# csc.net
KiCad netlist of a schematic drawn in EAGLE
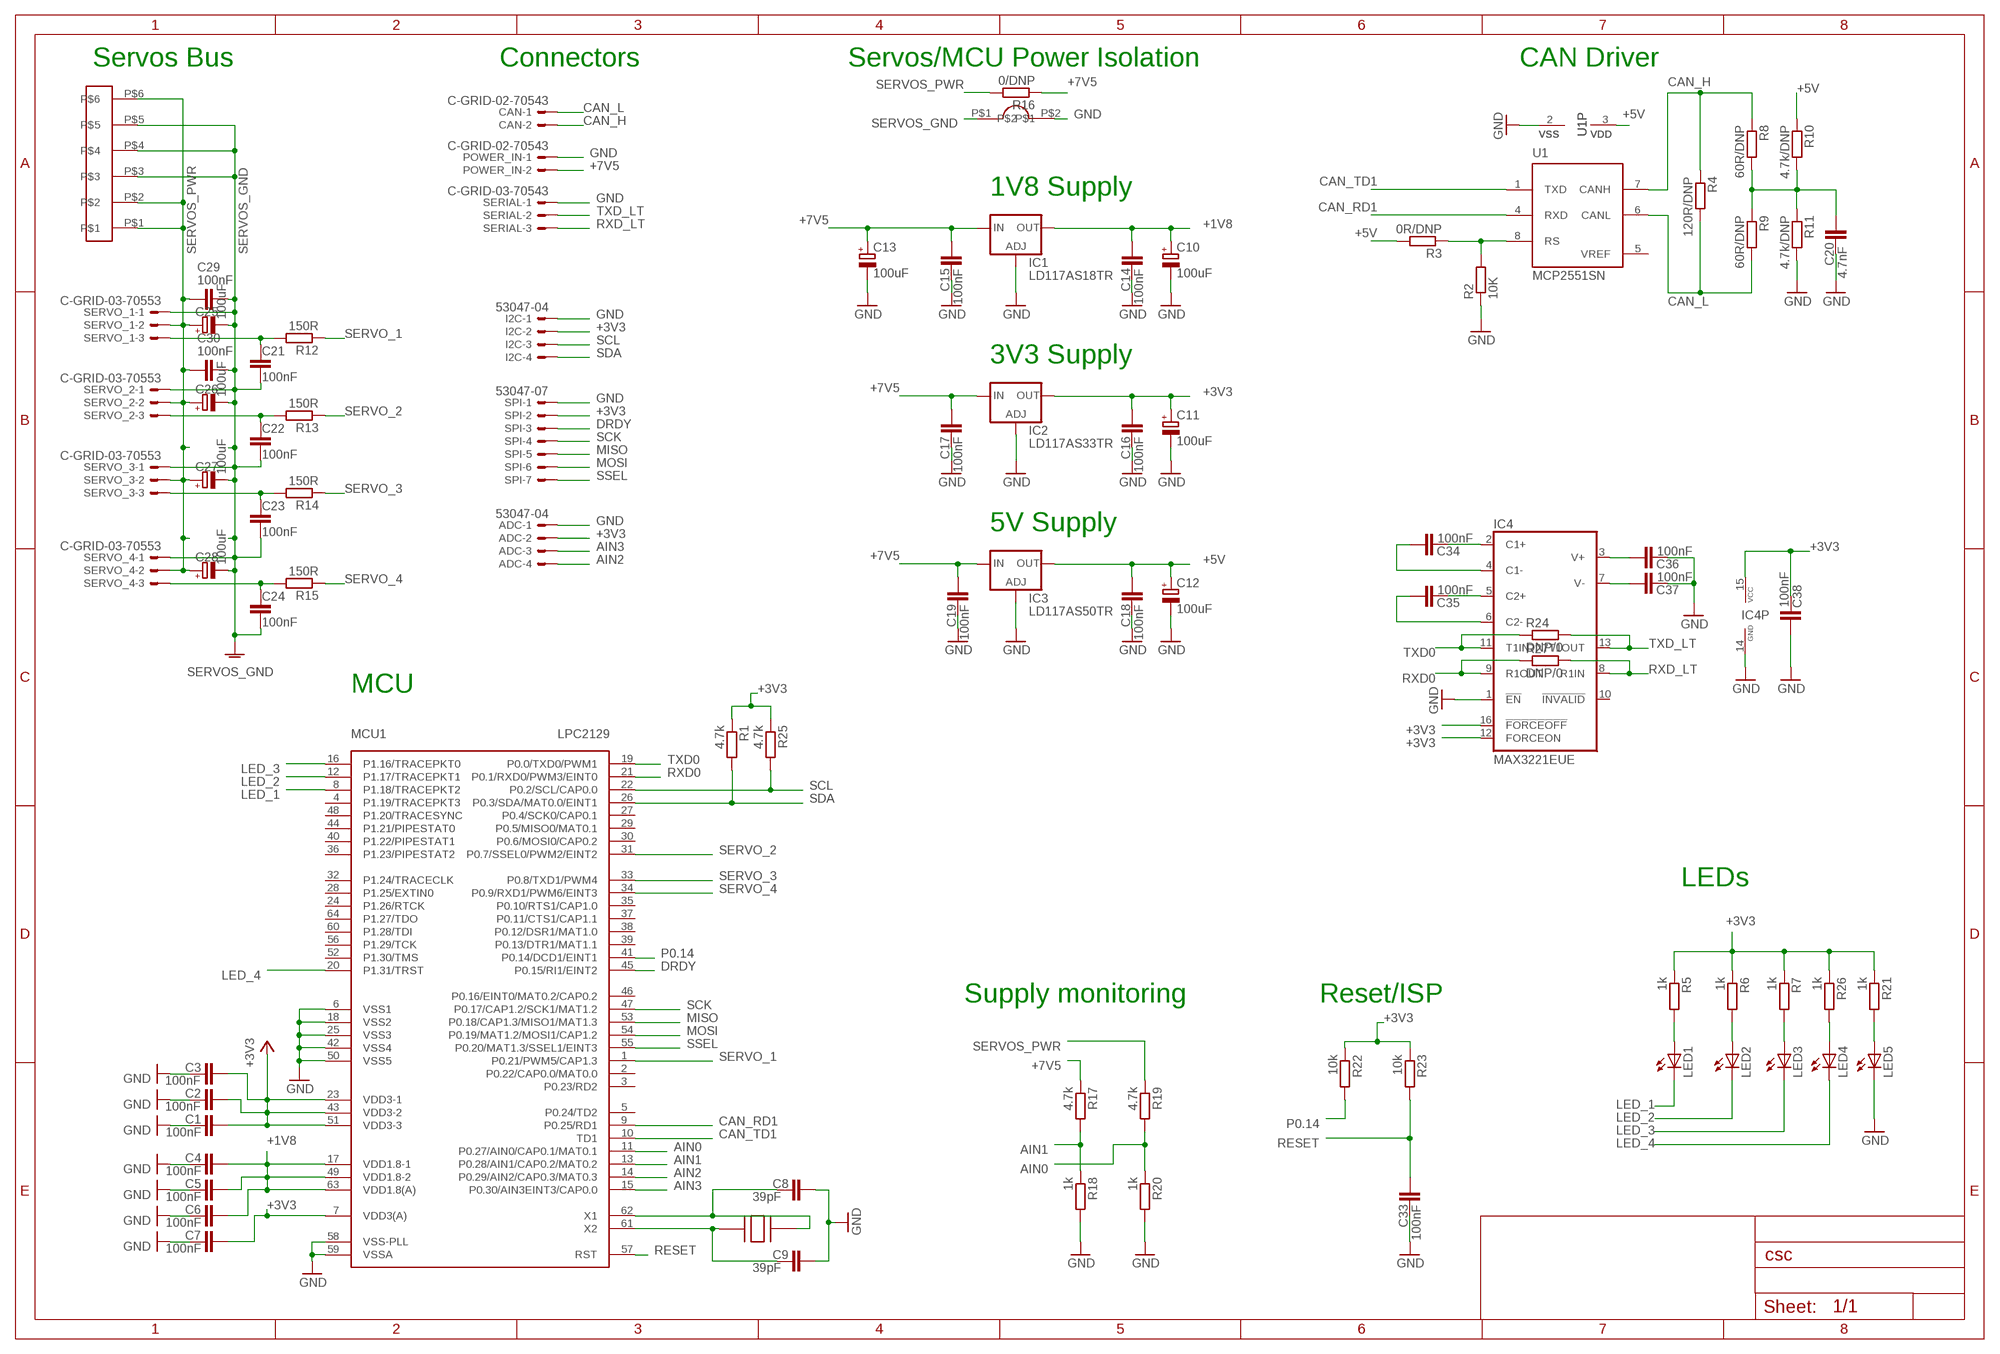
[diagram p0: schematic, sheet 1]

(export (version "E")
  (design (tool "Eeschema 10.0.6"))
  (components
    (comp (ref "ADC")
      (value "53047-04")
      (footprint "eagle-import:53047-04")
      (libsource (lib "eagle-import") (part "53?-04047"))
    )
    (comp (ref "C1")
      (value "100nF")
      (footprint "eagle-import:C0603K")
      (libsource (lib "eagle-import") (part "C-EUC0603K"))
    )
    (comp (ref "C2")
      (value "100nF")
      (footprint "eagle-import:C0603K")
      (libsource (lib "eagle-import") (part "C-EUC0603K"))
    )
    (comp (ref "C3")
      (value "100nF")
      (footprint "eagle-import:C0603K")
      (libsource (lib "eagle-import") (part "C-EUC0603K"))
    )
    (comp (ref "C4")
      (value "100nF")
      (footprint "eagle-import:C0603K")
      (libsource (lib "eagle-import") (part "C-EUC0603K"))
    )
    (comp (ref "C5")
      (value "100nF")
      (footprint "eagle-import:C0603K")
      (libsource (lib "eagle-import") (part "C-EUC0603K"))
    )
    (comp (ref "C6")
      (value "100nF")
      (footprint "eagle-import:C0603K")
      (libsource (lib "eagle-import") (part "C-EUC0603K"))
    )
    (comp (ref "C7")
      (value "100nF")
      (footprint "eagle-import:C0603K")
      (libsource (lib "eagle-import") (part "C-EUC0603K"))
    )
    (comp (ref "C8")
      (value "39pF")
      (footprint "eagle-import:C0603K")
      (libsource (lib "eagle-import") (part "C-EUC0603K"))
    )
    (comp (ref "C9")
      (value "39pF")
      (footprint "eagle-import:C0603K")
      (libsource (lib "eagle-import") (part "C-EUC0603K"))
    )
    (comp (ref "C10")
      (value "100uF")
      (footprint "eagle-import:CT6032")
      (libsource (lib "eagle-import") (part "CPOL-EUCT6032"))
    )
    (comp (ref "C11")
      (value "100uF")
      (footprint "eagle-import:CT6032")
      (libsource (lib "eagle-import") (part "CPOL-EUCT6032"))
    )
    (comp (ref "C12")
      (value "100uF")
      (footprint "eagle-import:CT6032")
      (libsource (lib "eagle-import") (part "CPOL-EUCT6032"))
    )
    (comp (ref "C13")
      (value "100uF")
      (footprint "eagle-import:CT7343")
      (libsource (lib "eagle-import") (part "CPOL-EUCT7343"))
    )
    (comp (ref "C14")
      (value "100nF")
      (footprint "eagle-import:C0603K")
      (libsource (lib "eagle-import") (part "C-EUC0603K"))
    )
    (comp (ref "C15")
      (value "100nF")
      (footprint "eagle-import:C0603K")
      (libsource (lib "eagle-import") (part "C-EUC0603K"))
    )
    (comp (ref "C16")
      (value "100nF")
      (footprint "eagle-import:C0603K")
      (libsource (lib "eagle-import") (part "C-EUC0603K"))
    )
    (comp (ref "C17")
      (value "100nF")
      (footprint "eagle-import:C0603K")
      (libsource (lib "eagle-import") (part "C-EUC0603K"))
    )
    (comp (ref "C18")
      (value "100nF")
      (footprint "eagle-import:C0603K")
      (libsource (lib "eagle-import") (part "C-EUC0603K"))
    )
    (comp (ref "C19")
      (value "100nF")
      (footprint "eagle-import:C0603K")
      (libsource (lib "eagle-import") (part "C-EUC0603K"))
    )
    (comp (ref "C20")
      (value "4.7nF")
      (footprint "eagle-import:C0603K")
      (libsource (lib "eagle-import") (part "C-EUC0603K"))
    )
    (comp (ref "C21")
      (value "100nF")
      (footprint "eagle-import:C0603K")
      (libsource (lib "eagle-import") (part "C-EUC0603K"))
    )
    (comp (ref "C22")
      (value "100nF")
      (footprint "eagle-import:C0603K")
      (libsource (lib "eagle-import") (part "C-EUC0603K"))
    )
    (comp (ref "C23")
      (value "100nF")
      (footprint "eagle-import:C0603K")
      (libsource (lib "eagle-import") (part "C-EUC0603K"))
    )
    (comp (ref "C24")
      (value "100nF")
      (footprint "eagle-import:C0603K")
      (libsource (lib "eagle-import") (part "C-EUC0603K"))
    )
    (comp (ref "C25")
      (value "100uF")
      (footprint "eagle-import:E_7260-38W")
      (libsource (lib "eagle-import") (part "CPOL-EUE/7260-38W"))
    )
    (comp (ref "C26")
      (value "100uF")
      (footprint "eagle-import:E_7260-38W")
      (libsource (lib "eagle-import") (part "CPOL-EUE/7260-38W"))
    )
    (comp (ref "C27")
      (value "100uF")
      (footprint "eagle-import:E_7260-38W")
      (libsource (lib "eagle-import") (part "CPOL-EUE/7260-38W"))
    )
    (comp (ref "C28")
      (value "100uF")
      (footprint "eagle-import:E_7260-38W")
      (libsource (lib "eagle-import") (part "CPOL-EUE/7260-38W"))
    )
    (comp (ref "C29")
      (value "100nF")
      (footprint "eagle-import:C0603K")
      (libsource (lib "eagle-import") (part "C-EUC0603K"))
    )
    (comp (ref "C30")
      (value "100nF")
      (footprint "eagle-import:C0603K")
      (libsource (lib "eagle-import") (part "C-EUC0603K"))
    )
    (comp (ref "C33")
      (value "100nF")
      (footprint "eagle-import:C0603K")
      (libsource (lib "eagle-import") (part "C-EUC0603K"))
    )
    (comp (ref "C34")
      (value "100nF")
      (footprint "eagle-import:C0603K")
      (libsource (lib "eagle-import") (part "C-EUC0603K"))
    )
    (comp (ref "C35")
      (value "100nF")
      (footprint "eagle-import:C0603K")
      (libsource (lib "eagle-import") (part "C-EUC0603K"))
    )
    (comp (ref "C36")
      (value "100nF")
      (footprint "eagle-import:C0603K")
      (libsource (lib "eagle-import") (part "C-EUC0603K"))
    )
    (comp (ref "C37")
      (value "100nF")
      (footprint "eagle-import:C0603K")
      (libsource (lib "eagle-import") (part "C-EUC0603K"))
    )
    (comp (ref "C38")
      (value "100nF")
      (footprint "eagle-import:C0603K")
      (libsource (lib "eagle-import") (part "C-EUC0603K"))
    )
    (comp (ref "CAN")
      (value "C-GRID-02-70543")
      (footprint "eagle-import:70543-02")
      (libsource (lib "eagle-import") (part "C-GRID-02-70543"))
    )
    (comp (ref "I2C")
      (value "53047-04")
      (footprint "eagle-import:53047-04")
      (libsource (lib "eagle-import") (part "53?-04047"))
    )
    (comp (ref "IC1")
      (value "LD117AS18TR")
      (footprint "eagle-import:SOT223")
      (libsource (lib "eagle-import") (part "LD117A?S18TR"))
    )
    (comp (ref "IC2")
      (value "LD117AS33TR")
      (footprint "eagle-import:SOT223")
      (libsource (lib "eagle-import") (part "LD117A?S33TR"))
    )
    (comp (ref "IC3")
      (value "LD117AS50TR")
      (footprint "eagle-import:SOT223")
      (libsource (lib "eagle-import") (part "LD117A?S50TR"))
    )
    (comp (ref "IC4")
      (value "MAX3221EUE")
      (footprint "eagle-import:TSSOP16")
      (libsource (lib "eagle-import") (part "MAX3221UEE"))
    )
    (comp (ref "LED1")
      (value "LEDCHIP-LED0805")
      (footprint "eagle-import:CHIP-LED0805")
      (libsource (lib "eagle-import") (part "LEDCHIP-LED0805"))
    )
    (comp (ref "LED2")
      (value "LEDCHIP-LED0805")
      (footprint "eagle-import:CHIP-LED0805")
      (libsource (lib "eagle-import") (part "LEDCHIP-LED0805"))
    )
    (comp (ref "LED3")
      (value "LEDCHIP-LED0805")
      (footprint "eagle-import:CHIP-LED0805")
      (libsource (lib "eagle-import") (part "LEDCHIP-LED0805"))
    )
    (comp (ref "LED4")
      (value "LEDCHIP-LED0805")
      (footprint "eagle-import:CHIP-LED0805")
      (libsource (lib "eagle-import") (part "LEDCHIP-LED0805"))
    )
    (comp (ref "LED5")
      (value "LEDCHIP-LED0805")
      (footprint "eagle-import:CHIP-LED0805")
      (libsource (lib "eagle-import") (part "LEDCHIP-LED0805"))
    )
    (comp (ref "MCU1")
      (value "LPC2129")
      (footprint "eagle-import:SQFP-S-10X10-64")
      (libsource (lib "eagle-import") (part "LPC2129"))
    )
    (comp (ref "POWER_IN")
      (value "C-GRID-02-70543")
      (footprint "eagle-import:70543-02")
      (libsource (lib "eagle-import") (part "C-GRID-02-70543"))
    )
    (comp (ref "R1")
      (value "4.7k")
      (footprint "eagle-import:R0603")
      (libsource (lib "eagle-import") (part "R-EU_R0603"))
    )
    (comp (ref "R2")
      (value "10K")
      (footprint "eagle-import:R0603")
      (libsource (lib "eagle-import") (part "R-EU_R0603"))
    )
    (comp (ref "R3")
      (value "0R/DNP")
      (footprint "eagle-import:R0603")
      (libsource (lib "eagle-import") (part "R-EU_R0603"))
    )
    (comp (ref "R4")
      (value "120R/DNP")
      (footprint "eagle-import:R0603")
      (libsource (lib "eagle-import") (part "R-EU_R0603"))
    )
    (comp (ref "R5")
      (value "1k")
      (footprint "eagle-import:R0603")
      (libsource (lib "eagle-import") (part "R-EU_R0603"))
    )
    (comp (ref "R6")
      (value "1k")
      (footprint "eagle-import:R0603")
      (libsource (lib "eagle-import") (part "R-EU_R0603"))
    )
    (comp (ref "R7")
      (value "1k")
      (footprint "eagle-import:R0603")
      (libsource (lib "eagle-import") (part "R-EU_R0603"))
    )
    (comp (ref "R8")
      (value "60R/DNP")
      (footprint "eagle-import:R0603")
      (libsource (lib "eagle-import") (part "R-EU_R0603"))
    )
    (comp (ref "R9")
      (value "60R/DNP")
      (footprint "eagle-import:R0603")
      (libsource (lib "eagle-import") (part "R-EU_R0603"))
    )
    (comp (ref "R10")
      (value "4.7k/DNP")
      (footprint "eagle-import:R0603")
      (libsource (lib "eagle-import") (part "R-EU_R0603"))
    )
    (comp (ref "R11")
      (value "4.7k/DNP")
      (footprint "eagle-import:R0603")
      (libsource (lib "eagle-import") (part "R-EU_R0603"))
    )
    (comp (ref "R12")
      (value "150R")
      (footprint "eagle-import:R0603")
      (libsource (lib "eagle-import") (part "R-EU_R0603"))
    )
    (comp (ref "R13")
      (value "150R")
      (footprint "eagle-import:R0603")
      (libsource (lib "eagle-import") (part "R-EU_R0603"))
    )
    (comp (ref "R14")
      (value "150R")
      (footprint "eagle-import:R0603")
      (libsource (lib "eagle-import") (part "R-EU_R0603"))
    )
    (comp (ref "R15")
      (value "150R")
      (footprint "eagle-import:R0603")
      (libsource (lib "eagle-import") (part "R-EU_R0603"))
    )
    (comp (ref "R16")
      (value "0/DNP")
      (footprint "eagle-import:R0603")
      (libsource (lib "eagle-import") (part "R-EU_R0603"))
    )
    (comp (ref "R17")
      (value "4.7k")
      (footprint "eagle-import:R0603")
      (libsource (lib "eagle-import") (part "R-EU_R0603"))
    )
    (comp (ref "R18")
      (value "1k")
      (footprint "eagle-import:R0603")
      (libsource (lib "eagle-import") (part "R-EU_R0603"))
    )
    (comp (ref "R19")
      (value "4.7k")
      (footprint "eagle-import:R0603")
      (libsource (lib "eagle-import") (part "R-EU_R0603"))
    )
    (comp (ref "R20")
      (value "1k")
      (footprint "eagle-import:R0603")
      (libsource (lib "eagle-import") (part "R-EU_R0603"))
    )
    (comp (ref "R21")
      (value "1k")
      (footprint "eagle-import:R0603")
      (libsource (lib "eagle-import") (part "R-EU_R0603"))
    )
    (comp (ref "R22")
      (value "10k")
      (footprint "eagle-import:R0603")
      (libsource (lib "eagle-import") (part "R-EU_R0603"))
    )
    (comp (ref "R23")
      (value "10k")
      (footprint "eagle-import:R0603")
      (libsource (lib "eagle-import") (part "R-EU_R0603"))
    )
    (comp (ref "R24")
      (value "DNP/0")
      (footprint "eagle-import:R0603")
      (libsource (lib "eagle-import") (part "R-EU_R0603"))
    )
    (comp (ref "R25")
      (value "4.7k")
      (footprint "eagle-import:R0603")
      (libsource (lib "eagle-import") (part "R-EU_R0603"))
    )
    (comp (ref "R26")
      (value "1k")
      (footprint "eagle-import:R0603")
      (libsource (lib "eagle-import") (part "R-EU_R0603"))
    )
    (comp (ref "R27")
      (value "DNP/0")
      (footprint "eagle-import:R0603")
      (libsource (lib "eagle-import") (part "R-EU_R0603"))
    )
    (comp (ref "SERIAL")
      (value "C-GRID-03-70543")
      (footprint "eagle-import:70543-03")
      (libsource (lib "eagle-import") (part "C-GRID-03-70543"))
    )
    (comp (ref "SERVO_1")
      (value "C-GRID-03-70553")
      (footprint "eagle-import:70553-03")
      (libsource (lib "eagle-import") (part "C-GRID-03-70553"))
    )
    (comp (ref "SERVO_2")
      (value "C-GRID-03-70553")
      (footprint "eagle-import:70553-03")
      (libsource (lib "eagle-import") (part "C-GRID-03-70553"))
    )
    (comp (ref "SERVO_3")
      (value "C-GRID-03-70553")
      (footprint "eagle-import:70553-03")
      (libsource (lib "eagle-import") (part "C-GRID-03-70553"))
    )
    (comp (ref "SERVO_4")
      (value "C-GRID-03-70553")
      (footprint "eagle-import:70553-03")
      (libsource (lib "eagle-import") (part "C-GRID-03-70553"))
    )
    (comp (ref "SPI")
      (value "53047-07")
      (footprint "eagle-import:53047-07")
      (libsource (lib "eagle-import") (part "53?-07047"))
    )
    (comp (ref "U$1")
      (value "CRYSTAL_CTS")
      (footprint "eagle-import:CTS_CRYSTAL")
      (libsource (lib "eagle-import") (part "CRYSTAL_CTS"))
    )
    (comp (ref "U$2")
      (value "CON_MPX")
      (footprint "eagle-import:CON_MPX")
      (libsource (lib "eagle-import") (part "CON_MPX"))
    )
    (comp (ref "U$3")
      (value "NULL_DEV")
      (footprint "eagle-import:NULL_DEV")
      (libsource (lib "eagle-import") (part "NULL_DEV"))
    )
    (comp (ref "U1")
      (value "MCP2551SN")
      (footprint "eagle-import:SO-08")
      (libsource (lib "eagle-import") (part "MCP2551SN"))
    )
  )
  (nets
    (net (code "1") (name "+3V3") (class "Default")
      (node (ref "ADC") (pin "2") (pinfunction "S_2") (pintype "passive"))
      (node (ref "C1") (pin "2") (pinfunction "2_2") (pintype "passive"))
      (node (ref "C11") (pin "+") (pinfunction "+_+") (pintype "passive"))
      (node (ref "C16") (pin "2") (pinfunction "2_2") (pintype "passive"))
      (node (ref "C2") (pin "2") (pinfunction "2_2") (pintype "passive"))
      (node (ref "C3") (pin "2") (pinfunction "2_2") (pintype "passive"))
      (node (ref "C38") (pin "1") (pinfunction "1_1") (pintype "passive"))
      (node (ref "C7") (pin "2") (pinfunction "2_2") (pintype "passive"))
      (node (ref "I2C") (pin "2") (pinfunction "S_2") (pintype "passive"))
      (node (ref "IC2") (pin "4") (pinfunction "OUT_4") (pintype "passive"))
      (node (ref "IC4") (pin "12") (pinfunction "FORCEON_12") (pintype "input"))
      (node (ref "IC4") (pin "15") (pinfunction "VCC_15") (pintype "power_in"))
      (node (ref "IC4") (pin "16") (pinfunction "~{FORCEOFF}_16") (pintype "input"))
      (node (ref "MCU1") (pin "23") (pinfunction "VDD3-1_23") (pintype "bidirectional"))
      (node (ref "MCU1") (pin "43") (pinfunction "VDD3-2_43") (pintype "bidirectional"))
      (node (ref "MCU1") (pin "51") (pinfunction "VDD3-3_51") (pintype "bidirectional"))
      (node (ref "MCU1") (pin "7") (pinfunction "VDD3(A)_7") (pintype "bidirectional"))
      (node (ref "R1") (pin "1") (pinfunction "1_1") (pintype "passive"))
      (node (ref "R21") (pin "1") (pinfunction "1_1") (pintype "passive"))
      (node (ref "R22") (pin "1") (pinfunction "1_1") (pintype "passive"))
      (node (ref "R23") (pin "1") (pinfunction "1_1") (pintype "passive"))
      (node (ref "R25") (pin "1") (pinfunction "1_1") (pintype "passive"))
      (node (ref "R26") (pin "1") (pinfunction "1_1") (pintype "passive"))
      (node (ref "R5") (pin "1") (pinfunction "1_1") (pintype "passive"))
      (node (ref "R6") (pin "1") (pinfunction "1_1") (pintype "passive"))
      (node (ref "R7") (pin "1") (pinfunction "1_1") (pintype "passive"))
      (node (ref "SPI") (pin "2") (pinfunction "S_2") (pintype "passive"))
    )
    (net (code "2") (name "/+1V8") (class "Default")
      (node (ref "C10") (pin "+") (pinfunction "+_+") (pintype "passive"))
      (node (ref "C14") (pin "2") (pinfunction "2_2") (pintype "passive"))
      (node (ref "C4") (pin "2") (pinfunction "2_2") (pintype "passive"))
      (node (ref "C5") (pin "2") (pinfunction "2_2") (pintype "passive"))
      (node (ref "C6") (pin "2") (pinfunction "2_2") (pintype "passive"))
      (node (ref "IC1") (pin "4") (pinfunction "OUT_4") (pintype "passive"))
      (node (ref "MCU1") (pin "17") (pinfunction "VDD1.8-1_17") (pintype "bidirectional"))
      (node (ref "MCU1") (pin "49") (pinfunction "VDD1.8-2_49") (pintype "bidirectional"))
      (node (ref "MCU1") (pin "63") (pinfunction "VDD1.8(A)_63") (pintype "bidirectional"))
    )
    (net (code "3") (name "/+5V") (class "Default")
      (node (ref "C12") (pin "+") (pinfunction "+_+") (pintype "passive"))
      (node (ref "C18") (pin "2") (pinfunction "2_2") (pintype "passive"))
      (node (ref "IC3") (pin "4") (pinfunction "OUT_4") (pintype "passive"))
      (node (ref "R10") (pin "1") (pinfunction "1_1") (pintype "passive"))
      (node (ref "R3") (pin "2") (pinfunction "2_2") (pintype "passive"))
      (node (ref "U1") (pin "3") (pinfunction "VDD_3") (pintype "power_in"))
    )
    (net (code "4") (name "/+7V5") (class "Default")
      (node (ref "C13") (pin "+") (pinfunction "+_+") (pintype "passive"))
      (node (ref "C15") (pin "2") (pinfunction "2_2") (pintype "passive"))
      (node (ref "C17") (pin "2") (pinfunction "2_2") (pintype "passive"))
      (node (ref "C19") (pin "2") (pinfunction "2_2") (pintype "passive"))
      (node (ref "IC1") (pin "3") (pinfunction "IN_3") (pintype "input"))
      (node (ref "IC2") (pin "3") (pinfunction "IN_3") (pintype "input"))
      (node (ref "IC3") (pin "3") (pinfunction "IN_3") (pintype "input"))
      (node (ref "POWER_IN") (pin "2") (pinfunction "S_2") (pintype "passive"))
      (node (ref "R16") (pin "1") (pinfunction "1_1") (pintype "passive"))
      (node (ref "R17") (pin "1") (pinfunction "1_1") (pintype "passive"))
    )
    (net (code "5") (name "/AIN0") (class "Default")
      (node (ref "MCU1") (pin "11") (pinfunction "P0.27/AIN0/CAP0.1/MAT0.1_11") (pintype "bidirectional"))
      (node (ref "R19") (pin "2") (pinfunction "2_2") (pintype "passive"))
      (node (ref "R20") (pin "1") (pinfunction "1_1") (pintype "passive"))
    )
    (net (code "6") (name "/AIN1") (class "Default")
      (node (ref "MCU1") (pin "13") (pinfunction "P0.28/AIN1/CAP0.2/MAT0.2_13") (pintype "bidirectional"))
      (node (ref "R17") (pin "2") (pinfunction "2_2") (pintype "passive"))
      (node (ref "R18") (pin "1") (pinfunction "1_1") (pintype "passive"))
    )
    (net (code "7") (name "/AIN2") (class "Default")
      (node (ref "ADC") (pin "4") (pinfunction "S_4") (pintype "passive"))
      (node (ref "MCU1") (pin "14") (pinfunction "P0.29/AIN2/CAP0.3/MAT0.3_14") (pintype "bidirectional"))
    )
    (net (code "8") (name "/AIN3") (class "Default")
      (node (ref "ADC") (pin "3") (pinfunction "S_3") (pintype "passive"))
      (node (ref "MCU1") (pin "15") (pinfunction "P0.30/AIN3EINT3/CAP0.0_15") (pintype "bidirectional"))
    )
    (net (code "9") (name "/CAN_H") (class "Default")
      (node (ref "CAN") (pin "2") (pinfunction "S_2") (pintype "passive"))
      (node (ref "R4") (pin "1") (pinfunction "1_1") (pintype "passive"))
      (node (ref "R8") (pin "1") (pinfunction "1_1") (pintype "passive"))
      (node (ref "U1") (pin "7") (pinfunction "CANH_7") (pintype "bidirectional"))
    )
    (net (code "10") (name "/CAN_L") (class "Default")
      (node (ref "CAN") (pin "1") (pinfunction "S_1") (pintype "passive"))
      (node (ref "R4") (pin "2") (pinfunction "2_2") (pintype "passive"))
      (node (ref "R9") (pin "2") (pinfunction "2_2") (pintype "passive"))
      (node (ref "U1") (pin "6") (pinfunction "CANL_6") (pintype "bidirectional"))
    )
    (net (code "11") (name "/CAN_RD1") (class "Default")
      (node (ref "MCU1") (pin "9") (pinfunction "P0.25/RD1_9") (pintype "bidirectional"))
      (node (ref "U1") (pin "4") (pinfunction "RXD_4") (pintype "output"))
    )
    (net (code "12") (name "/CAN_TD1") (class "Default")
      (node (ref "MCU1") (pin "10") (pinfunction "TD1_10") (pintype "bidirectional"))
      (node (ref "U1") (pin "1") (pinfunction "TXD_1") (pintype "input"))
    )
    (net (code "13") (name "/DRDY") (class "Default")
      (node (ref "MCU1") (pin "45") (pinfunction "P0.15/RI1/EINT2_45") (pintype "bidirectional"))
      (node (ref "SPI") (pin "3") (pinfunction "S_3") (pintype "passive"))
    )
    (net (code "14") (name "/LED_1") (class "Default")
      (node (ref "LED1") (pin "C") (pinfunction "C_C") (pintype "passive"))
      (node (ref "MCU1") (pin "8") (pinfunction "P1.18/TRACEPKT2_8") (pintype "bidirectional"))
    )
    (net (code "15") (name "/LED_2") (class "Default")
      (node (ref "LED2") (pin "C") (pinfunction "C_C") (pintype "passive"))
      (node (ref "MCU1") (pin "12") (pinfunction "P1.17/TRACEPKT1_12") (pintype "bidirectional"))
    )
    (net (code "16") (name "/LED_3") (class "Default")
      (node (ref "LED3") (pin "C") (pinfunction "C_C") (pintype "passive"))
      (node (ref "MCU1") (pin "16") (pinfunction "P1.16/TRACEPKT0_16") (pintype "bidirectional"))
    )
    (net (code "17") (name "/LED_4") (class "Default")
      (node (ref "LED4") (pin "C") (pinfunction "C_C") (pintype "passive"))
      (node (ref "MCU1") (pin "20") (pinfunction "P1.31/TRST_20") (pintype "bidirectional"))
    )
    (net (code "18") (name "/MISO") (class "Default")
      (node (ref "MCU1") (pin "53") (pinfunction "P0.18/CAP1.3/MISO1/MAT1.3_53") (pintype "bidirectional"))
      (node (ref "SPI") (pin "5") (pinfunction "S_5") (pintype "passive"))
    )
    (net (code "19") (name "/MOSI") (class "Default")
      (node (ref "MCU1") (pin "54") (pinfunction "P0.19/MAT1.2/MOSI1/CAP1.2_54") (pintype "bidirectional"))
      (node (ref "SPI") (pin "6") (pinfunction "S_6") (pintype "passive"))
    )
    (net (code "20") (name "/P0.14") (class "Default")
      (node (ref "MCU1") (pin "41") (pinfunction "P0.14/DCD1/EINT1_41") (pintype "bidirectional"))
      (node (ref "R22") (pin "2") (pinfunction "2_2") (pintype "passive"))
    )
    (net (code "21") (name "/RESET") (class "Default")
      (node (ref "C33") (pin "2") (pinfunction "2_2") (pintype "passive"))
      (node (ref "MCU1") (pin "57") (pinfunction "RST_57") (pintype "bidirectional"))
      (node (ref "R23") (pin "2") (pinfunction "2_2") (pintype "passive"))
    )
    (net (code "22") (name "/RXD0") (class "Default")
      (node (ref "IC4") (pin "9") (pinfunction "R1OUT_9") (pintype "output"))
      (node (ref "MCU1") (pin "21") (pinfunction "P0.1/RXD0/PWM3/EINT0_21") (pintype "bidirectional"))
      (node (ref "R27") (pin "1") (pinfunction "1_1") (pintype "passive"))
    )
    (net (code "23") (name "/RXD_LT") (class "Default")
      (node (ref "IC4") (pin "8") (pinfunction "R1IN_8") (pintype "input"))
      (node (ref "R27") (pin "2") (pinfunction "2_2") (pintype "passive"))
      (node (ref "SERIAL") (pin "3") (pinfunction "S_3") (pintype "passive"))
    )
    (net (code "24") (name "/SCK") (class "Default")
      (node (ref "MCU1") (pin "47") (pinfunction "P0.17/CAP1.2/SCK1/MAT1.2_47") (pintype "bidirectional"))
      (node (ref "SPI") (pin "4") (pinfunction "S_4") (pintype "passive"))
    )
    (net (code "25") (name "/SCL") (class "Default")
      (node (ref "I2C") (pin "3") (pinfunction "S_3") (pintype "passive"))
      (node (ref "MCU1") (pin "22") (pinfunction "P0.2/SCL/CAP0.0_22") (pintype "bidirectional"))
      (node (ref "R25") (pin "2") (pinfunction "2_2") (pintype "passive"))
    )
    (net (code "26") (name "/SDA") (class "Default")
      (node (ref "I2C") (pin "4") (pinfunction "S_4") (pintype "passive"))
      (node (ref "MCU1") (pin "26") (pinfunction "P0.3/SDA/MAT0.0/EINT1_26") (pintype "bidirectional"))
      (node (ref "R1") (pin "2") (pinfunction "2_2") (pintype "passive"))
    )
    (net (code "27") (name "/SERVOS_PWR") (class "Default")
      (node (ref "C25") (pin "+") (pinfunction "+_+") (pintype "passive"))
      (node (ref "C26") (pin "+") (pinfunction "+_+") (pintype "passive"))
      (node (ref "C27") (pin "+") (pinfunction "+_+") (pintype "passive"))
      (node (ref "C28") (pin "+") (pinfunction "+_+") (pintype "passive"))
      (node (ref "C29") (pin "2") (pinfunction "2_2") (pintype "passive"))
      (node (ref "C30") (pin "2") (pinfunction "2_2") (pintype "passive"))
      (node (ref "R16") (pin "2") (pinfunction "2_2") (pintype "passive"))
      (node (ref "R19") (pin "1") (pinfunction "1_1") (pintype "passive"))
      (node (ref "SERVO_1") (pin "2") (pinfunction "S_2") (pintype "passive"))
      (node (ref "SERVO_2") (pin "2") (pinfunction "S_2") (pintype "passive"))
      (node (ref "SERVO_3") (pin "2") (pinfunction "S_2") (pintype "passive"))
      (node (ref "SERVO_4") (pin "2") (pinfunction "S_2") (pintype "passive"))
      (node (ref "U$2") (pin "P$1") (pinfunction "P$1_P$1") (pintype "bidirectional"))
      (node (ref "U$2") (pin "P$2") (pinfunction "P$2_P$2") (pintype "bidirectional"))
      (node (ref "U$2") (pin "P$6") (pinfunction "P$6_P$6") (pintype "bidirectional"))
    )
    (net (code "28") (name "/SERVO_1") (class "Default")
      (node (ref "MCU1") (pin "1") (pinfunction "P0.21/PWM5/CAP1.3_1") (pintype "bidirectional"))
      (node (ref "R12") (pin "1") (pinfunction "1_1") (pintype "passive"))
    )
    (net (code "29") (name "/SERVO_2") (class "Default")
      (node (ref "MCU1") (pin "31") (pinfunction "P0.7/SSEL0/PWM2/EINT2_31") (pintype "bidirectional"))
      (node (ref "R13") (pin "1") (pinfunction "1_1") (pintype "passive"))
    )
    (net (code "30") (name "/SERVO_3") (class "Default")
      (node (ref "MCU1") (pin "33") (pinfunction "P0.8/TXD1/PWM4_33") (pintype "bidirectional"))
      (node (ref "R14") (pin "1") (pinfunction "1_1") (pintype "passive"))
    )
    (net (code "31") (name "/SERVO_4") (class "Default")
      (node (ref "MCU1") (pin "34") (pinfunction "P0.9/RXD1/PWM6/EINT3_34") (pintype "bidirectional"))
      (node (ref "R15") (pin "1") (pinfunction "1_1") (pintype "passive"))
    )
    (net (code "32") (name "/SSEL") (class "Default")
      (node (ref "MCU1") (pin "55") (pinfunction "P0.20/MAT1.3/SSEL1/EINT3_55") (pintype "bidirectional"))
      (node (ref "SPI") (pin "7") (pinfunction "S_7") (pintype "passive"))
    )
    (net (code "33") (name "/TXD0") (class "Default")
      (node (ref "IC4") (pin "11") (pinfunction "T1IN_11") (pintype "input"))
      (node (ref "MCU1") (pin "19") (pinfunction "P0.0/TXD0/PWM1_19") (pintype "bidirectional"))
      (node (ref "R24") (pin "1") (pinfunction "1_1") (pintype "passive"))
    )
    (net (code "34") (name "/TXD_LT") (class "Default")
      (node (ref "IC4") (pin "13") (pinfunction "T1OUT_13") (pintype "output"))
      (node (ref "R24") (pin "2") (pinfunction "2_2") (pintype "passive"))
      (node (ref "SERIAL") (pin "2") (pinfunction "S_2") (pintype "passive"))
    )
    (net (code "35") (name "/VREF") (class "Default")
      (node (ref "U1") (pin "5") (pinfunction "VREF_5") (pintype "power_in"))
    )
    (net (code "36") (name "GND") (class "Default")
      (node (ref "ADC") (pin "1") (pinfunction "S_1") (pintype "passive"))
      (node (ref "C1") (pin "1") (pinfunction "1_1") (pintype "passive"))
      (node (ref "C10") (pin "-") (pinfunction "-_-") (pintype "passive"))
      (node (ref "C11") (pin "-") (pinfunction "-_-") (pintype "passive"))
      (node (ref "C12") (pin "-") (pinfunction "-_-") (pintype "passive"))
      (node (ref "C13") (pin "-") (pinfunction "-_-") (pintype "passive"))
      (node (ref "C14") (pin "1") (pinfunction "1_1") (pintype "passive"))
      (node (ref "C15") (pin "1") (pinfunction "1_1") (pintype "passive"))
      (node (ref "C16") (pin "1") (pinfunction "1_1") (pintype "passive"))
      (node (ref "C17") (pin "1") (pinfunction "1_1") (pintype "passive"))
      (node (ref "C18") (pin "1") (pinfunction "1_1") (pintype "passive"))
      (node (ref "C19") (pin "1") (pinfunction "1_1") (pintype "passive"))
      (node (ref "C2") (pin "1") (pinfunction "1_1") (pintype "passive"))
      (node (ref "C20") (pin "1") (pinfunction "1_1") (pintype "passive"))
      (node (ref "C3") (pin "1") (pinfunction "1_1") (pintype "passive"))
      (node (ref "C33") (pin "1") (pinfunction "1_1") (pintype "passive"))
      (node (ref "C36") (pin "1") (pinfunction "1_1") (pintype "passive"))
      (node (ref "C37") (pin "1") (pinfunction "1_1") (pintype "passive"))
      (node (ref "C38") (pin "2") (pinfunction "2_2") (pintype "passive"))
      (node (ref "C4") (pin "1") (pinfunction "1_1") (pintype "passive"))
      (node (ref "C5") (pin "1") (pinfunction "1_1") (pintype "passive"))
      (node (ref "C6") (pin "1") (pinfunction "1_1") (pintype "passive"))
      (node (ref "C7") (pin "1") (pinfunction "1_1") (pintype "passive"))
      (node (ref "C8") (pin "2") (pinfunction "2_2") (pintype "passive"))
      (node (ref "C9") (pin "2") (pinfunction "2_2") (pintype "passive"))
      (node (ref "I2C") (pin "1") (pinfunction "S_1") (pintype "passive"))
      (node (ref "IC1") (pin "1") (pinfunction "ADJ_1") (pintype "input"))
      (node (ref "IC2") (pin "1") (pinfunction "ADJ_1") (pintype "input"))
      (node (ref "IC3") (pin "1") (pinfunction "ADJ_1") (pintype "input"))
      (node (ref "IC4") (pin "1") (pinfunction "~{EN}_1") (pintype "input"))
      (node (ref "IC4") (pin "14") (pinfunction "GND_14") (pintype "power_in"))
      (node (ref "LED5") (pin "C") (pinfunction "C_C") (pintype "passive"))
      (node (ref "MCU1") (pin "18") (pinfunction "VSS2_18") (pintype "bidirectional"))
      (node (ref "MCU1") (pin "25") (pinfunction "VSS3_25") (pintype "bidirectional"))
      (node (ref "MCU1") (pin "42") (pinfunction "VSS4_42") (pintype "bidirectional"))
      (node (ref "MCU1") (pin "50") (pinfunction "VSS5_50") (pintype "bidirectional"))
      (node (ref "MCU1") (pin "58") (pinfunction "VSS-PLL_58") (pintype "bidirectional"))
      (node (ref "MCU1") (pin "59") (pinfunction "VSSA_59") (pintype "bidirectional"))
      (node (ref "MCU1") (pin "6") (pinfunction "VSS1_6") (pintype "bidirectional"))
      (node (ref "POWER_IN") (pin "1") (pinfunction "S_1") (pintype "passive"))
      (node (ref "R11") (pin "2") (pinfunction "2_2") (pintype "passive"))
      (node (ref "R18") (pin "2") (pinfunction "2_2") (pintype "passive"))
      (node (ref "R2") (pin "1") (pinfunction "1_1") (pintype "passive"))
      (node (ref "R20") (pin "2") (pinfunction "2_2") (pintype "passive"))
      (node (ref "SERIAL") (pin "1") (pinfunction "S_1") (pintype "passive"))
      (node (ref "SPI") (pin "1") (pinfunction "S_1") (pintype "passive"))
      (node (ref "U$3") (pin "P$2") (pinfunction "P$2_P$2") (pintype "bidirectional"))
      (node (ref "U1") (pin "2") (pinfunction "VSS_2") (pintype "power_in"))
    )
    (net (code "37") (name "Net-(C20-Pad2)") (class "Default")
      (node (ref "C20") (pin "2") (pinfunction "2_2") (pintype "passive"))
      (node (ref "R10") (pin "2") (pinfunction "2_2") (pintype "passive"))
      (node (ref "R11") (pin "1") (pinfunction "1_1") (pintype "passive"))
      (node (ref "R8") (pin "2") (pinfunction "2_2") (pintype "passive"))
      (node (ref "R9") (pin "1") (pinfunction "1_1") (pintype "passive"))
    )
    (net (code "38") (name "Net-(IC4A-C1+)") (class "Default")
      (node (ref "C34") (pin "1") (pinfunction "1_1") (pintype "passive"))
      (node (ref "IC4") (pin "2") (pinfunction "C1+_2") (pintype "passive"))
    )
    (net (code "39") (name "Net-(IC4A-C1-)") (class "Default")
      (node (ref "C34") (pin "2") (pinfunction "2_2") (pintype "passive"))
      (node (ref "IC4") (pin "4") (pinfunction "C1-_4") (pintype "passive"))
    )
    (net (code "40") (name "Net-(IC4A-C2+)") (class "Default")
      (node (ref "C35") (pin "1") (pinfunction "1_1") (pintype "passive"))
      (node (ref "IC4") (pin "5") (pinfunction "C2+_5") (pintype "passive"))
    )
    (net (code "41") (name "Net-(IC4A-C2-)") (class "Default")
      (node (ref "C35") (pin "2") (pinfunction "2_2") (pintype "passive"))
      (node (ref "IC4") (pin "6") (pinfunction "C2-_6") (pintype "passive"))
    )
    (net (code "42") (name "Net-(IC4A-V+)") (class "Default")
      (node (ref "C36") (pin "2") (pinfunction "2_2") (pintype "passive"))
      (node (ref "IC4") (pin "3") (pinfunction "V+_3") (pintype "passive"))
    )
    (net (code "43") (name "Net-(IC4A-V-)") (class "Default")
      (node (ref "C37") (pin "2") (pinfunction "2_2") (pintype "passive"))
      (node (ref "IC4") (pin "7") (pinfunction "V-_7") (pintype "passive"))
    )
    (net (code "44") (name "Net-(LED1-PadA)") (class "Default")
      (node (ref "LED1") (pin "A") (pinfunction "A_A") (pintype "passive"))
      (node (ref "R5") (pin "2") (pinfunction "2_2") (pintype "passive"))
    )
    (net (code "45") (name "Net-(LED2-PadA)") (class "Default")
      (node (ref "LED2") (pin "A") (pinfunction "A_A") (pintype "passive"))
      (node (ref "R6") (pin "2") (pinfunction "2_2") (pintype "passive"))
    )
    (net (code "46") (name "Net-(LED3-PadA)") (class "Default")
      (node (ref "LED3") (pin "A") (pinfunction "A_A") (pintype "passive"))
      (node (ref "R7") (pin "2") (pinfunction "2_2") (pintype "passive"))
    )
    (net (code "47") (name "Net-(LED4-PadA)") (class "Default")
      (node (ref "LED4") (pin "A") (pinfunction "A_A") (pintype "passive"))
      (node (ref "R26") (pin "2") (pinfunction "2_2") (pintype "passive"))
    )
    (net (code "48") (name "Net-(LED5-PadA)") (class "Default")
      (node (ref "LED5") (pin "A") (pinfunction "A_A") (pintype "passive"))
      (node (ref "R21") (pin "2") (pinfunction "2_2") (pintype "passive"))
    )
    (net (code "49") (name "Net-(MCU1-X1)") (class "Default")
      (node (ref "C8") (pin "1") (pinfunction "1_1") (pintype "passive"))
      (node (ref "MCU1") (pin "62") (pinfunction "X1_62") (pintype "bidirectional"))
      (node (ref "U$1") (pin "P$1") (pinfunction "P$1_P$1") (pintype "bidirectional"))
    )
    (net (code "50") (name "Net-(MCU1-X2)") (class "Default")
      (node (ref "C9") (pin "1") (pinfunction "1_1") (pintype "passive"))
      (node (ref "MCU1") (pin "61") (pinfunction "X2_61") (pintype "bidirectional"))
      (node (ref "U$1") (pin "P$3") (pinfunction "P$2_P$3") (pintype "bidirectional"))
    )
    (net (code "51") (name "Net-(SERVO_1C-S)") (class "Default")
      (node (ref "C21") (pin "2") (pinfunction "2_2") (pintype "passive"))
      (node (ref "R12") (pin "2") (pinfunction "2_2") (pintype "passive"))
      (node (ref "SERVO_1") (pin "3") (pinfunction "S_3") (pintype "passive"))
    )
    (net (code "52") (name "Net-(SERVO_2C-S)") (class "Default")
      (node (ref "C22") (pin "2") (pinfunction "2_2") (pintype "passive"))
      (node (ref "R13") (pin "2") (pinfunction "2_2") (pintype "passive"))
      (node (ref "SERVO_2") (pin "3") (pinfunction "S_3") (pintype "passive"))
    )
    (net (code "53") (name "Net-(SERVO_3C-S)") (class "Default")
      (node (ref "C23") (pin "2") (pinfunction "2_2") (pintype "passive"))
      (node (ref "R14") (pin "2") (pinfunction "2_2") (pintype "passive"))
      (node (ref "SERVO_3") (pin "3") (pinfunction "S_3") (pintype "passive"))
    )
    (net (code "54") (name "Net-(SERVO_4C-S)") (class "Default")
      (node (ref "C24") (pin "2") (pinfunction "2_2") (pintype "passive"))
      (node (ref "R15") (pin "2") (pinfunction "2_2") (pintype "passive"))
      (node (ref "SERVO_4") (pin "3") (pinfunction "S_3") (pintype "passive"))
    )
    (net (code "55") (name "Net-(U1A-RS)") (class "Default")
      (node (ref "R2") (pin "2") (pinfunction "2_2") (pintype "passive"))
      (node (ref "R3") (pin "1") (pinfunction "1_1") (pintype "passive"))
      (node (ref "U1") (pin "8") (pinfunction "RS_8") (pintype "input"))
    )
    (net (code "56") (name "SERVOS_GND") (class "Default")
      (node (ref "C21") (pin "1") (pinfunction "1_1") (pintype "passive"))
      (node (ref "C22") (pin "1") (pinfunction "1_1") (pintype "passive"))
      (node (ref "C23") (pin "1") (pinfunction "1_1") (pintype "passive"))
      (node (ref "C24") (pin "1") (pinfunction "1_1") (pintype "passive"))
      (node (ref "C25") (pin "-") (pinfunction "-_-") (pintype "passive"))
      (node (ref "C26") (pin "-") (pinfunction "-_-") (pintype "passive"))
      (node (ref "C27") (pin "-") (pinfunction "-_-") (pintype "passive"))
      (node (ref "C28") (pin "-") (pinfunction "-_-") (pintype "passive"))
      (node (ref "C29") (pin "1") (pinfunction "1_1") (pintype "passive"))
      (node (ref "C30") (pin "1") (pinfunction "1_1") (pintype "passive"))
      (node (ref "SERVO_1") (pin "1") (pinfunction "S_1") (pintype "passive"))
      (node (ref "SERVO_2") (pin "1") (pinfunction "S_1") (pintype "passive"))
      (node (ref "SERVO_3") (pin "1") (pinfunction "S_1") (pintype "passive"))
      (node (ref "SERVO_4") (pin "1") (pinfunction "S_1") (pintype "passive"))
      (node (ref "U$2") (pin "P$3") (pinfunction "P$3_P$3") (pintype "bidirectional"))
      (node (ref "U$2") (pin "P$4") (pinfunction "P$4_P$4") (pintype "bidirectional"))
      (node (ref "U$2") (pin "P$5") (pinfunction "P$5_P$5") (pintype "bidirectional"))
      (node (ref "U$3") (pin "P$1") (pinfunction "P$1_P$1") (pintype "bidirectional"))
    )
    (net (code "57") (name "unconnected-(IC4A-~{INVALID}-Pad10)") (class "Default")
      (node (ref "IC4") (pin "10") (pinfunction "~{INVALID}_10") (pintype "input"))
    )
    (net (code "58") (name "unconnected-(MCU1-P0.4{slash}SCK0{slash}CAP0.1-Pad27)") (class "Default")
      (node (ref "MCU1") (pin "27") (pinfunction "P0.4/SCK0/CAP0.1_27") (pintype "bidirectional"))
    )
    (net (code "59") (name "unconnected-(MCU1-P0.5{slash}MISO0{slash}MAT0.1-Pad29)") (class "Default")
      (node (ref "MCU1") (pin "29") (pinfunction "P0.5/MISO0/MAT0.1_29") (pintype "bidirectional"))
    )
    (net (code "60") (name "unconnected-(MCU1-P0.6{slash}MOSI0{slash}CAP0.2-Pad30)") (class "Default")
      (node (ref "MCU1") (pin "30") (pinfunction "P0.6/MOSI0/CAP0.2_30") (pintype "bidirectional"))
    )
    (net (code "61") (name "unconnected-(MCU1-P0.10{slash}RTS1{slash}CAP1.0-Pad35)") (class "Default")
      (node (ref "MCU1") (pin "35") (pinfunction "P0.10/RTS1/CAP1.0_35") (pintype "bidirectional"))
    )
    (net (code "62") (name "unconnected-(MCU1-P0.11{slash}CTS1{slash}CAP1.1-Pad37)") (class "Default")
      (node (ref "MCU1") (pin "37") (pinfunction "P0.11/CTS1/CAP1.1_37") (pintype "bidirectional"))
    )
    (net (code "63") (name "unconnected-(MCU1-P0.12{slash}DSR1{slash}MAT1.0-Pad38)") (class "Default")
      (node (ref "MCU1") (pin "38") (pinfunction "P0.12/DSR1/MAT1.0_38") (pintype "bidirectional"))
    )
    (net (code "64") (name "unconnected-(MCU1-P0.13{slash}DTR1{slash}MAT1.1-Pad39)") (class "Default")
      (node (ref "MCU1") (pin "39") (pinfunction "P0.13/DTR1/MAT1.1_39") (pintype "bidirectional"))
    )
    (net (code "65") (name "unconnected-(MCU1-P0.16{slash}EINT0{slash}MAT0.2{slash}CAP0.2-Pad46)") (class "Default")
      (node (ref "MCU1") (pin "46") (pinfunction "P0.16/EINT0/MAT0.2/CAP0.2_46") (pintype "bidirectional"))
    )
    (net (code "66") (name "unconnected-(MCU1-P0.22{slash}CAP0.0{slash}MAT0.0-Pad2)") (class "Default")
      (node (ref "MCU1") (pin "2") (pinfunction "P0.22/CAP0.0/MAT0.0_2") (pintype "bidirectional"))
    )
    (net (code "67") (name "unconnected-(MCU1-P0.23{slash}RD2-Pad3)") (class "Default")
      (node (ref "MCU1") (pin "3") (pinfunction "P0.23/RD2_3") (pintype "bidirectional"))
    )
    (net (code "68") (name "unconnected-(MCU1-P0.24{slash}TD2-Pad5)") (class "Default")
      (node (ref "MCU1") (pin "5") (pinfunction "P0.24/TD2_5") (pintype "bidirectional"))
    )
    (net (code "69") (name "unconnected-(MCU1-P1.19{slash}TRACEPKT3-Pad4)") (class "Default")
      (node (ref "MCU1") (pin "4") (pinfunction "P1.19/TRACEPKT3_4") (pintype "bidirectional"))
    )
    (net (code "70") (name "unconnected-(MCU1-P1.20{slash}TRACESYNC-Pad48)") (class "Default")
      (node (ref "MCU1") (pin "48") (pinfunction "P1.20/TRACESYNC_48") (pintype "bidirectional"))
    )
    (net (code "71") (name "unconnected-(MCU1-P1.21{slash}PIPESTAT0-Pad44)") (class "Default")
      (node (ref "MCU1") (pin "44") (pinfunction "P1.21/PIPESTAT0_44") (pintype "bidirectional"))
    )
    (net (code "72") (name "unconnected-(MCU1-P1.22{slash}PIPESTAT1-Pad40)") (class "Default")
      (node (ref "MCU1") (pin "40") (pinfunction "P1.22/PIPESTAT1_40") (pintype "bidirectional"))
    )
    (net (code "73") (name "unconnected-(MCU1-P1.23{slash}PIPESTAT2-Pad36)") (class "Default")
      (node (ref "MCU1") (pin "36") (pinfunction "P1.23/PIPESTAT2_36") (pintype "bidirectional"))
    )
    (net (code "74") (name "unconnected-(MCU1-P1.24{slash}TRACECLK-Pad32)") (class "Default")
      (node (ref "MCU1") (pin "32") (pinfunction "P1.24/TRACECLK_32") (pintype "bidirectional"))
    )
    (net (code "75") (name "unconnected-(MCU1-P1.25{slash}EXTIN0-Pad28)") (class "Default")
      (node (ref "MCU1") (pin "28") (pinfunction "P1.25/EXTIN0_28") (pintype "bidirectional"))
    )
    (net (code "76") (name "unconnected-(MCU1-P1.26{slash}RTCK-Pad24)") (class "Default")
      (node (ref "MCU1") (pin "24") (pinfunction "P1.26/RTCK_24") (pintype "bidirectional"))
    )
    (net (code "77") (name "unconnected-(MCU1-P1.27{slash}TDO-Pad64)") (class "Default")
      (node (ref "MCU1") (pin "64") (pinfunction "P1.27/TDO_64") (pintype "bidirectional"))
    )
    (net (code "78") (name "unconnected-(MCU1-P1.28{slash}TDI-Pad60)") (class "Default")
      (node (ref "MCU1") (pin "60") (pinfunction "P1.28/TDI_60") (pintype "bidirectional"))
    )
    (net (code "79") (name "unconnected-(MCU1-P1.29{slash}TCK-Pad56)") (class "Default")
      (node (ref "MCU1") (pin "56") (pinfunction "P1.29/TCK_56") (pintype "bidirectional"))
    )
    (net (code "80") (name "unconnected-(MCU1-P1.30{slash}TMS-Pad52)") (class "Default")
      (node (ref "MCU1") (pin "52") (pinfunction "P1.30/TMS_52") (pintype "bidirectional"))
    )
  )
)
